# PianoDIY.net
KiCad netlist of a schematic drawn in EAGLE
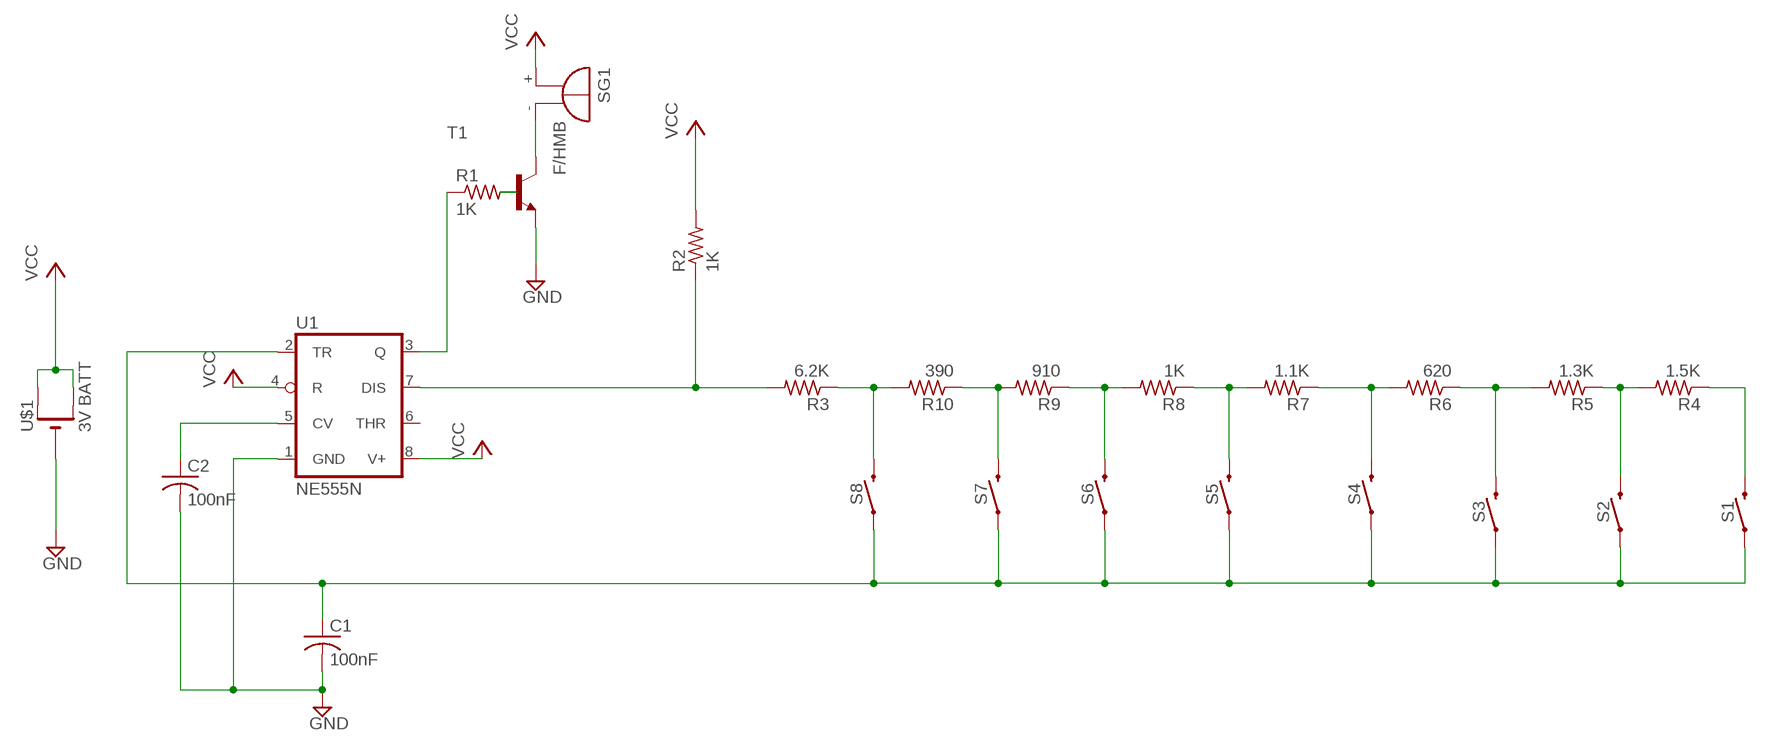
[diagram p0: schematic, sheet 1]

(export (version "E")
  (design (tool "Eeschema 10.0.6"))
  (components
    (comp (ref "C1")
      (value "100nF")
      (footprint "eagle-import:C025-025X050")
      (libsource (lib "eagle-import") (part "C-US025-025X050"))
    )
    (comp (ref "C2")
      (value "100nF")
      (footprint "eagle-import:C025-025X050")
      (libsource (lib "eagle-import") (part "C-US025-025X050"))
    )
    (comp (ref "R1")
      (value "1K")
      (footprint "eagle-import:0207_10")
      (libsource (lib "eagle-import") (part "R-US_0207/10"))
    )
    (comp (ref "R2")
      (value "1K")
      (footprint "eagle-import:0207_10")
      (libsource (lib "eagle-import") (part "R-US_0207/10"))
    )
    (comp (ref "R3")
      (value "6.2K")
      (footprint "eagle-import:0207_10")
      (libsource (lib "eagle-import") (part "R-US_0207/10"))
    )
    (comp (ref "R4")
      (value "1.5K")
      (footprint "eagle-import:0207_10")
      (libsource (lib "eagle-import") (part "R-US_0207/10"))
    )
    (comp (ref "R5")
      (value "1.3K")
      (footprint "eagle-import:0207_10")
      (libsource (lib "eagle-import") (part "R-US_0207/10"))
    )
    (comp (ref "R6")
      (value "620")
      (footprint "eagle-import:0207_10")
      (libsource (lib "eagle-import") (part "R-US_0207/10"))
    )
    (comp (ref "R7")
      (value "1.1K")
      (footprint "eagle-import:0207_10")
      (libsource (lib "eagle-import") (part "R-US_0207/10"))
    )
    (comp (ref "R8")
      (value "1K")
      (footprint "eagle-import:0207_10")
      (libsource (lib "eagle-import") (part "R-US_0207/10"))
    )
    (comp (ref "R9")
      (value "910")
      (footprint "eagle-import:0207_10")
      (libsource (lib "eagle-import") (part "R-US_0207/10"))
    )
    (comp (ref "R10")
      (value "390")
      (footprint "eagle-import:0207_10")
      (libsource (lib "eagle-import") (part "R-US_0207/10"))
    )
    (comp (ref "S1")
      (value "MOMENTARY-SWITCH-SPST-PTH-6.0MM")
      (footprint "eagle-import:TACTILE_SWITCH_PTH_6.0MM")
      (libsource (lib "eagle-import") (part "MOMENTARY-SWITCH-SPST-PTH-6.0MM"))
    )
    (comp (ref "S2")
      (value "MOMENTARY-SWITCH-SPST-PTH-6.0MM")
      (footprint "eagle-import:TACTILE_SWITCH_PTH_6.0MM")
      (libsource (lib "eagle-import") (part "MOMENTARY-SWITCH-SPST-PTH-6.0MM"))
    )
    (comp (ref "S3")
      (value "MOMENTARY-SWITCH-SPST-PTH-6.0MM")
      (footprint "eagle-import:TACTILE_SWITCH_PTH_6.0MM")
      (libsource (lib "eagle-import") (part "MOMENTARY-SWITCH-SPST-PTH-6.0MM"))
    )
    (comp (ref "S4")
      (value "MOMENTARY-SWITCH-SPST-PTH-6.0MM")
      (footprint "eagle-import:TACTILE_SWITCH_PTH_6.0MM")
      (libsource (lib "eagle-import") (part "MOMENTARY-SWITCH-SPST-PTH-6.0MM"))
    )
    (comp (ref "S5")
      (value "MOMENTARY-SWITCH-SPST-PTH-6.0MM")
      (footprint "eagle-import:TACTILE_SWITCH_PTH_6.0MM")
      (libsource (lib "eagle-import") (part "MOMENTARY-SWITCH-SPST-PTH-6.0MM"))
    )
    (comp (ref "S6")
      (value "MOMENTARY-SWITCH-SPST-PTH-6.0MM")
      (footprint "eagle-import:TACTILE_SWITCH_PTH_6.0MM")
      (libsource (lib "eagle-import") (part "MOMENTARY-SWITCH-SPST-PTH-6.0MM"))
    )
    (comp (ref "S7")
      (value "MOMENTARY-SWITCH-SPST-PTH-6.0MM")
      (footprint "eagle-import:TACTILE_SWITCH_PTH_6.0MM")
      (libsource (lib "eagle-import") (part "MOMENTARY-SWITCH-SPST-PTH-6.0MM"))
    )
    (comp (ref "S8")
      (value "MOMENTARY-SWITCH-SPST-PTH-6.0MM")
      (footprint "eagle-import:TACTILE_SWITCH_PTH_6.0MM")
      (libsource (lib "eagle-import") (part "MOMENTARY-SWITCH-SPST-PTH-6.0MM"))
    )
    (comp (ref "SG1")
      (value "F/HMB")
      (footprint "eagle-import:F_HMB")
      (libsource (lib "eagle-import") (part "F/HMB"))
    )
    (comp (ref "T1")
      (value "-NPN-TO92-E1")
      (footprint "eagle-import:TO92-E1")
      (libsource (lib "eagle-import") (part "-NPN-TO92-E1"))
    )
    (comp (ref "U$1")
      (value "3V BATT")
      (footprint "eagle-import:CR1220-THM")
      (libsource (lib "eagle-import") (part "CR1220THM"))
    )
    (comp (ref "U1")
      (value "NE555N")
      (footprint "eagle-import:DIL08")
      (fields (field (name "SPICEPREFIX") "X"))
      (libsource (lib "eagle-import") (part "555NNE"))
    )
  )
  (nets
    (net (code "1") (name "GND") (class "Default")
      (node (ref "C1") (pin "2") (pinfunction "2_2") (pintype "passive"))
      (node (ref "C2") (pin "2") (pinfunction "2_2") (pintype "passive"))
      (node (ref "T1") (pin "3") (pinfunction "E_3") (pintype "passive"))
      (node (ref "U$1") (pin "-") (pinfunction "-_-") (pintype "passive"))
      (node (ref "U1") (pin "1") (pinfunction "GND_1") (pintype "power_in"))
    )
    (net (code "2") (name "Net-(S1-2)") (class "Default")
      (node (ref "R4") (pin "1") (pinfunction "1_1") (pintype "passive"))
      (node (ref "S1") (pin "3") (pinfunction "2_3") (pintype "passive"))
    )
    (net (code "3") (name "Net-(S2-2)") (class "Default")
      (node (ref "R4") (pin "2") (pinfunction "2_2") (pintype "passive"))
      (node (ref "R5") (pin "1") (pinfunction "1_1") (pintype "passive"))
      (node (ref "S2") (pin "3") (pinfunction "2_3") (pintype "passive"))
    )
    (net (code "4") (name "Net-(S3-2)") (class "Default")
      (node (ref "R5") (pin "2") (pinfunction "2_2") (pintype "passive"))
      (node (ref "R6") (pin "1") (pinfunction "1_1") (pintype "passive"))
      (node (ref "S3") (pin "3") (pinfunction "2_3") (pintype "passive"))
    )
    (net (code "5") (name "Net-(S4-2)") (class "Default")
      (node (ref "R6") (pin "2") (pinfunction "2_2") (pintype "passive"))
      (node (ref "R7") (pin "1") (pinfunction "1_1") (pintype "passive"))
      (node (ref "S4") (pin "3") (pinfunction "2_3") (pintype "passive"))
    )
    (net (code "6") (name "Net-(S5-2)") (class "Default")
      (node (ref "R7") (pin "2") (pinfunction "2_2") (pintype "passive"))
      (node (ref "R8") (pin "1") (pinfunction "1_1") (pintype "passive"))
      (node (ref "S5") (pin "3") (pinfunction "2_3") (pintype "passive"))
    )
    (net (code "7") (name "Net-(S6-2)") (class "Default")
      (node (ref "R8") (pin "2") (pinfunction "2_2") (pintype "passive"))
      (node (ref "R9") (pin "1") (pinfunction "1_1") (pintype "passive"))
      (node (ref "S6") (pin "3") (pinfunction "2_3") (pintype "passive"))
    )
    (net (code "8") (name "Net-(S7-2)") (class "Default")
      (node (ref "R10") (pin "1") (pinfunction "1_1") (pintype "passive"))
      (node (ref "R9") (pin "2") (pinfunction "2_2") (pintype "passive"))
      (node (ref "S7") (pin "3") (pinfunction "2_3") (pintype "passive"))
    )
    (net (code "9") (name "Net-(S8-2)") (class "Default")
      (node (ref "R10") (pin "2") (pinfunction "2_2") (pintype "passive"))
      (node (ref "R3") (pin "1") (pinfunction "1_1") (pintype "passive"))
      (node (ref "S8") (pin "3") (pinfunction "2_3") (pintype "passive"))
    )
    (net (code "10") (name "Net-(T1-B)") (class "Default")
      (node (ref "R1") (pin "2") (pinfunction "2_2") (pintype "passive"))
      (node (ref "T1") (pin "2") (pinfunction "B_2") (pintype "passive"))
    )
    (net (code "11") (name "Net-(T1-C)") (class "Default")
      (node (ref "SG1") (pin "-") (pinfunction "-_-") (pintype "passive"))
      (node (ref "T1") (pin "1") (pinfunction "C_1") (pintype "passive"))
    )
    (net (code "12") (name "Net-(U1-CV)") (class "Default")
      (node (ref "C2") (pin "1") (pinfunction "1_1") (pintype "passive"))
      (node (ref "U1") (pin "5") (pinfunction "CV_5") (pintype "input"))
    )
    (net (code "13") (name "Net-(U1-DIS)") (class "Default")
      (node (ref "R2") (pin "1") (pinfunction "1_1") (pintype "passive"))
      (node (ref "R3") (pin "2") (pinfunction "2_2") (pintype "passive"))
      (node (ref "U1") (pin "7") (pinfunction "DIS_7") (pintype "input"))
    )
    (net (code "14") (name "Net-(U1-Q)") (class "Default")
      (node (ref "R1") (pin "1") (pinfunction "1_1") (pintype "passive"))
      (node (ref "U1") (pin "3") (pinfunction "Q_3") (pintype "output"))
    )
    (net (code "15") (name "Net-(U1-TR)") (class "Default")
      (node (ref "C1") (pin "1") (pinfunction "1_1") (pintype "passive"))
      (node (ref "S1") (pin "1") (pinfunction "1_1") (pintype "passive"))
      (node (ref "S2") (pin "1") (pinfunction "1_1") (pintype "passive"))
      (node (ref "S3") (pin "1") (pinfunction "1_1") (pintype "passive"))
      (node (ref "S4") (pin "1") (pinfunction "1_1") (pintype "passive"))
      (node (ref "S5") (pin "1") (pinfunction "1_1") (pintype "passive"))
      (node (ref "S6") (pin "1") (pinfunction "1_1") (pintype "passive"))
      (node (ref "S7") (pin "1") (pinfunction "1_1") (pintype "passive"))
      (node (ref "S8") (pin "1") (pinfunction "1_1") (pintype "passive"))
      (node (ref "U1") (pin "2") (pinfunction "TR_2") (pintype "input"))
    )
    (net (code "16") (name "VCC") (class "Default")
      (node (ref "R2") (pin "2") (pinfunction "2_2") (pintype "passive"))
      (node (ref "SG1") (pin "+") (pinfunction "+_+") (pintype "passive"))
      (node (ref "U$1") (pin "+1") (pinfunction "+_+1") (pintype "passive"))
      (node (ref "U$1") (pin "+2") (pinfunction "+1_+2") (pintype "passive"))
      (node (ref "U1") (pin "4") (pinfunction "R_4") (pintype "input"))
      (node (ref "U1") (pin "8") (pinfunction "V+_8") (pintype "power_in"))
    )
    (net (code "17") (name "unconnected-(U1-THR-Pad6)") (class "Default")
      (node (ref "U1") (pin "6") (pinfunction "THR_6") (pintype "input"))
    )
  )
)
